# 02_ZYNQ_PS-BANK500-501.net
KiCad netlist of a schematic drawn in Altium Designer
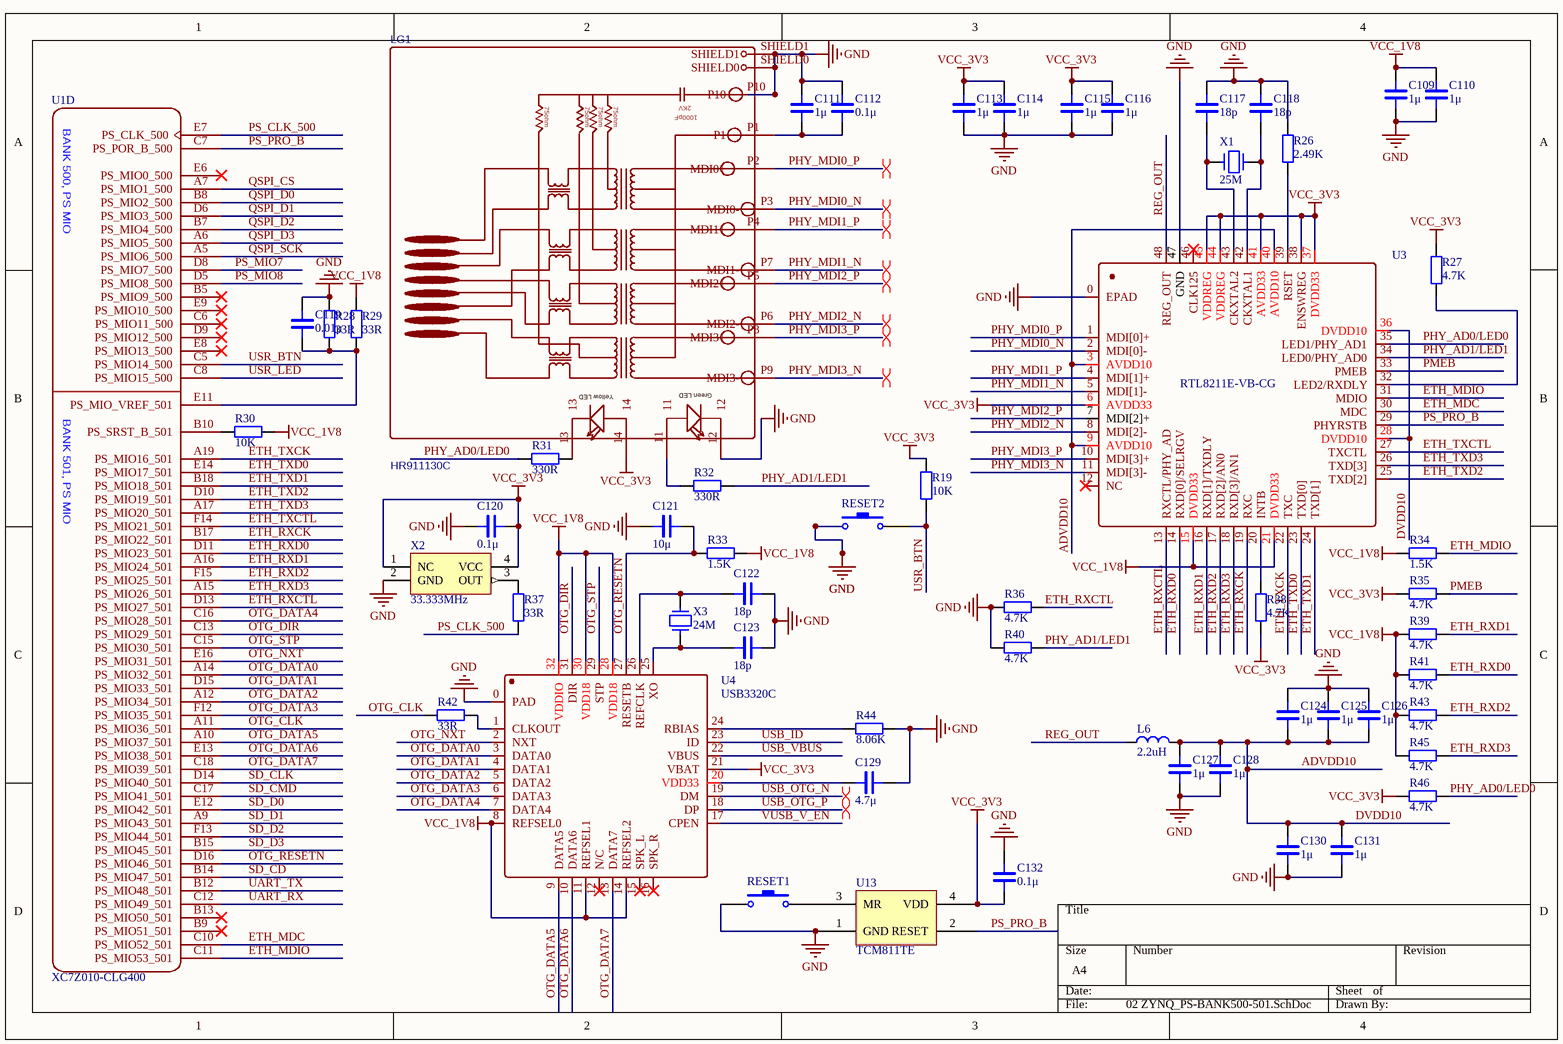
[diagram p0: 02 ZYNQ_PS-BANK500-501.SchDoc]

(export (version "E")
  (design (tool "Eeschema 10.0.6"))
  (components
    (comp (ref "C109")
      (value "1μ")
      (footprint "LC-0402_C")
      (description "Capacitor")
      (libsource (lib "DDR3_xc7z010-clg400") (part "CAP_2"))
    )
    (comp (ref "C110")
      (value "1μ")
      (footprint "LC-0402_C")
      (description "Capacitor")
      (libsource (lib "DDR3_xc7z010-clg400") (part "CAP_2"))
    )
    (comp (ref "C111")
      (value "1μ")
      (footprint "LC-0402_C")
      (description "Capacitor")
      (libsource (lib "DDR3_xc7z010-clg400") (part "CAP_2"))
    )
    (comp (ref "C112")
      (value "0.1μ")
      (footprint "LC-0402_C")
      (description "Capacitor")
      (libsource (lib "DDR3_xc7z010-clg400") (part "CAP_2"))
    )
    (comp (ref "C113")
      (value "1μ")
      (footprint "LC-0402_C")
      (description "Capacitor")
      (libsource (lib "DDR3_xc7z010-clg400") (part "CAP_2"))
    )
    (comp (ref "C114")
      (value "1μ")
      (footprint "LC-0402_C")
      (description "Capacitor")
      (libsource (lib "DDR3_xc7z010-clg400") (part "CAP_2"))
    )
    (comp (ref "C115")
      (value "1μ")
      (footprint "LC-0402_C")
      (description "Capacitor")
      (libsource (lib "DDR3_xc7z010-clg400") (part "CAP_2"))
    )
    (comp (ref "C116")
      (value "1μ")
      (footprint "LC-0402_C")
      (description "Capacitor")
      (libsource (lib "DDR3_xc7z010-clg400") (part "CAP_2"))
    )
    (comp (ref "C117")
      (value "18p")
      (footprint "LC-0402_C")
      (description "Capacitor")
      (libsource (lib "DDR3_xc7z010-clg400") (part "CAP_1"))
    )
    (comp (ref "C118")
      (value "18p")
      (footprint "LC-0402_C")
      (description "Capacitor")
      (libsource (lib "DDR3_xc7z010-clg400") (part "CAP_1"))
    )
    (comp (ref "C119")
      (value "0.01μ")
      (footprint "LC-0402_C")
      (description "Capacitor")
      (libsource (lib "DDR3_xc7z010-clg400") (part "CAP_2"))
    )
    (comp (ref "C120")
      (value "0.1μ")
      (footprint "LC-0402_C")
      (description "Capacitor")
      (libsource (lib "DDR3_xc7z010-clg400") (part "CAP_2"))
    )
    (comp (ref "C121")
      (value "10μ")
      (footprint "LC-0402_C")
      (description "Capacitor")
      (libsource (lib "DDR3_xc7z010-clg400") (part "CAP_2"))
    )
    (comp (ref "C122")
      (value "18p")
      (footprint "LC-0402_C")
      (description "Capacitor")
      (libsource (lib "DDR3_xc7z010-clg400") (part "CAP_1"))
    )
    (comp (ref "C123")
      (value "18p")
      (footprint "LC-0402_C")
      (description "Capacitor")
      (libsource (lib "DDR3_xc7z010-clg400") (part "CAP_1"))
    )
    (comp (ref "C124")
      (value "1μ")
      (footprint "LC-0402_C")
      (description "Capacitor")
      (libsource (lib "DDR3_xc7z010-clg400") (part "CAP_2"))
    )
    (comp (ref "C125")
      (value "1μ")
      (footprint "LC-0402_C")
      (description "Capacitor")
      (libsource (lib "DDR3_xc7z010-clg400") (part "CAP_2"))
    )
    (comp (ref "C126")
      (value "1μ")
      (footprint "LC-0402_C")
      (description "Capacitor")
      (libsource (lib "DDR3_xc7z010-clg400") (part "CAP_2"))
    )
    (comp (ref "C127")
      (value "1μ")
      (footprint "LC-0402_C")
      (description "Capacitor")
      (libsource (lib "DDR3_xc7z010-clg400") (part "CAP_2"))
    )
    (comp (ref "C128")
      (value "1μ")
      (footprint "LC-0402_C")
      (description "Capacitor")
      (libsource (lib "DDR3_xc7z010-clg400") (part "CAP_2"))
    )
    (comp (ref "C129")
      (value "4.7μ")
      (footprint "LC-0402_C")
      (description "Capacitor")
      (libsource (lib "DDR3_xc7z010-clg400") (part "CAP_2"))
    )
    (comp (ref "C130")
      (value "1μ")
      (footprint "LC-0402_C")
      (description "Capacitor")
      (libsource (lib "DDR3_xc7z010-clg400") (part "CAP_2"))
    )
    (comp (ref "C131")
      (value "1μ")
      (footprint "LC-0402_C")
      (description "Capacitor")
      (libsource (lib "DDR3_xc7z010-clg400") (part "CAP_2"))
    )
    (comp (ref "C132")
      (value "0.1μ")
      (footprint "LC-0402_C")
      (description "Capacitor")
      (libsource (lib "DDR3_xc7z010-clg400") (part "CAP_2"))
    )
    (comp (ref "L6")
      (value "2.2uH")
      (footprint "L1008")
      (description "Inductance")
      (libsource (lib "NGFF_M_Key_xc7z010-clg400") (part "INDUCTANCE_1"))
    )
    (comp (ref "LG1")
      (value "HR911130C")
      (footprint "HR911130C")
      (fields (field (name "BOM_SUPPLIER PART") "C50933") (field (name "CONTRIBUTOR") "LCSC"))
      (libsource (lib "AD9363_ZYNQ_V2") (part "HR911130C"))
    )
    (comp (ref "R19")
      (value "10K")
      (footprint "LC-0402_R")
      (description "Resistor")
      (libsource (lib "DDR3_xc7z010-clg400") (part "RES"))
    )
    (comp (ref "R26")
      (value "2.49K")
      (footprint "LC-0402_R")
      (description "Resistor")
      (libsource (lib "") (part "RES_2"))
    )
    (comp (ref "R27")
      (value "4.7K")
      (footprint "LC-0402_R")
      (description "Resistor")
      (libsource (lib "") (part "RES_2"))
    )
    (comp (ref "R28")
      (value "33R")
      (footprint "LC-0402_R")
      (description "Resistor")
      (libsource (lib "") (part "RES_2"))
    )
    (comp (ref "R29")
      (value "33R")
      (footprint "LC-0402_R")
      (description "Resistor")
      (libsource (lib "") (part "RES_2"))
    )
    (comp (ref "R30")
      (value "10K")
      (footprint "LC-0402_R")
      (description "Resistor")
      (libsource (lib "") (part "RES_1"))
    )
    (comp (ref "R31")
      (value "330R")
      (footprint "LC-0402_R")
      (description "Resistor")
      (libsource (lib "") (part "RES_3"))
    )
    (comp (ref "R32")
      (value "330R")
      (footprint "LC-0402_R")
      (description "Resistor")
      (libsource (lib "") (part "RES_1"))
    )
    (comp (ref "R33")
      (value "1.5K")
      (footprint "LC-0402_R")
      (description "Resistor")
      (libsource (lib "") (part "RES_3"))
    )
    (comp (ref "R34")
      (value "1.5K")
      (footprint "LC-0402_R")
      (description "Resistor")
      (libsource (lib "") (part "RES_3"))
    )
    (comp (ref "R35")
      (value "4.7K")
      (footprint "LC-0402_R")
      (description "Resistor")
      (libsource (lib "") (part "RES_3"))
    )
    (comp (ref "R36")
      (value "4.7K")
      (footprint "LC-0402_R")
      (description "Resistor")
      (libsource (lib "") (part "RES_3"))
    )
    (comp (ref "R37")
      (value "33R")
      (footprint "LC-0402_R")
      (description "Resistor")
      (libsource (lib "") (part "RES_2"))
    )
    (comp (ref "R38")
      (value "4.7K")
      (footprint "LC-0402_R")
      (description "Resistor")
      (libsource (lib "") (part "RES_2"))
    )
    (comp (ref "R39")
      (value "4.7K")
      (footprint "LC-0402_R")
      (description "Resistor")
      (libsource (lib "") (part "RES_1"))
    )
    (comp (ref "R40")
      (value "4.7K")
      (footprint "LC-0402_R")
      (description "Resistor")
      (libsource (lib "") (part "RES_3"))
    )
    (comp (ref "R41")
      (value "4.7K")
      (footprint "LC-0402_R")
      (description "Resistor")
      (libsource (lib "") (part "RES_1"))
    )
    (comp (ref "R42")
      (value "33R")
      (footprint "LC-0402_R")
      (description "Resistor")
      (libsource (lib "") (part "RES_3"))
    )
    (comp (ref "R43")
      (value "4.7K")
      (footprint "LC-0402_R")
      (description "Resistor")
      (libsource (lib "") (part "RES_1"))
    )
    (comp (ref "R44")
      (value "8.06K")
      (footprint "LC-0402_R")
      (description "Resistor")
      (libsource (lib "") (part "RES_3"))
    )
    (comp (ref "R45")
      (value "4.7K")
      (footprint "LC-0402_R")
      (description "Resistor")
      (libsource (lib "") (part "RES_1"))
    )
    (comp (ref "R46")
      (value "4.7K")
      (footprint "LC-0402_R")
      (description "Resistor")
      (libsource (lib "") (part "RES_3"))
    )
    (comp (ref "RESET1")
      (value "SW-PB")
      (footprint "开关")
      (description "Switch")
      (fields (field (name "PUBLISHER") "Altium Limited"))
      (libsource (lib "PCB_Project") (part "SW-PB"))
    )
    (comp (ref "RESET2")
      (value "SW-PB")
      (footprint "开关")
      (description "Switch")
      (fields (field (name "PUBLISHER") "Altium Limited"))
      (libsource (lib "M4(3333)") (part "SW-PB"))
    )
    (comp (ref "U1")
      (value "XC7Z010-CLG400")
      (footprint "CLG400-0.8")
      (libsource (lib "DDR3_xc7z010-clg400") (part "XC7Z010-CLG400"))
    )
    (comp (ref "U3")
      (value "RTL8211E-VB-CG")
      (footprint "LC-QFN-48_6x6x04P")
      (libsource (lib "NGFF_M_Key_xc7z010-clg400") (part "RTL8211E-VB-CG"))
    )
    (comp (ref "U4")
      (value "USB3320C")
      (footprint "LC-QFN-32_5x5x05P")
      (libsource (lib "NGFF_M_Key_xc7z010-clg400") (part "USB3320C"))
    )
    (comp (ref "U13")
      (value "TCM811TE")
      (footprint "TCM811TERCTR")
      (libsource (lib "PCB_Project") (part "TCM811TE"))
    )
    (comp (ref "X1")
      (value "25M")
      (footprint "LC-SMD-5032_2P")
      (description "Crystal")
      (libsource (lib "DDR3_xc7z010-clg400") (part "XTAL-2"))
    )
    (comp (ref "X2")
      (value "33.333MHz")
      (footprint "OSC-SMD_4P-L3.2-W2.5-BL")
      (description "Oscillator")
      (libsource (lib "DDR3_xc7z010-clg400") (part "XTAL-4"))
    )
    (comp (ref "X3")
      (value "24M")
      (footprint "LC-SMD-5032_2P")
      (description "Crystal")
      (libsource (lib "DDR3_xc7z010-clg400") (part "XTAL-2"))
    )
  )
  (nets
    (net (code "1") (name "/ADVDD10") (class "Default")
      (node (ref "C124") (pin "1") (pinfunction "1_1") (pintype "passive"))
      (node (ref "C125") (pin "1") (pinfunction "1_1") (pintype "passive"))
      (node (ref "C126") (pin "1") (pinfunction "1_1") (pintype "passive"))
      (node (ref "C127") (pin "2") (pinfunction "2_2") (pintype "passive"))
      (node (ref "C128") (pin "2") (pinfunction "2_2") (pintype "passive"))
      (node (ref "C130") (pin "2") (pinfunction "2_2") (pintype "passive"))
      (node (ref "C131") (pin "2") (pinfunction "2_2") (pintype "passive"))
      (node (ref "L6") (pin "2") (pinfunction "2_2") (pintype "passive"))
      (node (ref "U3") (pin "28") (pinfunction "DVDD10_28") (pintype "passive"))
      (node (ref "U3") (pin "3") (pinfunction "AVDD10_3") (pintype "passive"))
      (node (ref "U3") (pin "36") (pinfunction "DVDD10_36") (pintype "passive"))
      (node (ref "U3") (pin "40") (pinfunction "AVDD10_40") (pintype "passive"))
      (node (ref "U3") (pin "9") (pinfunction "AVDD10_9") (pintype "passive"))
    )
    (net (code "2") (name "/ETH_MDC") (class "Default")
      (node (ref "U1") (pin "C10") (pinfunction "PS_MIO52_501_C10") (pintype "passive"))
      (node (ref "U3") (pin "30") (pinfunction "MDC_30") (pintype "passive"))
    )
    (net (code "3") (name "/ETH_MDIO") (class "Default")
      (node (ref "R34") (pin "2") (pinfunction "2_2") (pintype "passive"))
      (node (ref "U1") (pin "C11") (pinfunction "PS_MIO53_501_C11") (pintype "passive"))
      (node (ref "U3") (pin "31") (pinfunction "MDIO_31") (pintype "passive"))
    )
    (net (code "4") (name "/ETH_RXCK") (class "Default")
      (node (ref "U1") (pin "B17") (pinfunction "PS_MIO22_501_B17") (pintype "passive"))
      (node (ref "U3") (pin "19") (pinfunction "RXC_19") (pintype "passive"))
    )
    (net (code "5") (name "/ETH_RXCTL") (class "Default")
      (node (ref "R36") (pin "2") (pinfunction "2_2") (pintype "passive"))
      (node (ref "U1") (pin "D13") (pinfunction "PS_MIO27_501_D13") (pintype "passive"))
      (node (ref "U3") (pin "13") (pinfunction "RXCTL/PHY_AD_13") (pintype "passive"))
    )
    (net (code "6") (name "/ETH_RXD0") (class "Default")
      (node (ref "R41") (pin "1") (pinfunction "1_1") (pintype "passive"))
      (node (ref "U1") (pin "D11") (pinfunction "PS_MIO23_501_D11") (pintype "passive"))
      (node (ref "U3") (pin "14") (pinfunction "RXD[0]/SELRGV_14") (pintype "passive"))
    )
    (net (code "7") (name "/ETH_RXD1") (class "Default")
      (node (ref "R39") (pin "1") (pinfunction "1_1") (pintype "passive"))
      (node (ref "U1") (pin "A16") (pinfunction "PS_MIO24_501_A16") (pintype "passive"))
      (node (ref "U3") (pin "16") (pinfunction "RXD[1]/TXDLY_16") (pintype "passive"))
    )
    (net (code "8") (name "/ETH_RXD2") (class "Default")
      (node (ref "R43") (pin "1") (pinfunction "1_1") (pintype "passive"))
      (node (ref "U1") (pin "F15") (pinfunction "PS_MIO25_501_F15") (pintype "passive"))
      (node (ref "U3") (pin "17") (pinfunction "RXD[2]/AN0_17") (pintype "passive"))
    )
    (net (code "9") (name "/ETH_RXD3") (class "Default")
      (node (ref "R45") (pin "1") (pinfunction "1_1") (pintype "passive"))
      (node (ref "U1") (pin "A15") (pinfunction "PS_MIO26_501_A15") (pintype "passive"))
      (node (ref "U3") (pin "18") (pinfunction "RXD[3]/AN1_18") (pintype "passive"))
    )
    (net (code "10") (name "/ETH_TXCK") (class "Default")
      (node (ref "U1") (pin "A19") (pinfunction "PS_MIO16_501_A19") (pintype "passive"))
      (node (ref "U3") (pin "22") (pinfunction "TXC_22") (pintype "passive"))
    )
    (net (code "11") (name "/ETH_TXCTL") (class "Default")
      (node (ref "U1") (pin "F14") (pinfunction "PS_MIO21_501_F14") (pintype "passive"))
      (node (ref "U3") (pin "27") (pinfunction "TXCTL_27") (pintype "passive"))
    )
    (net (code "12") (name "/ETH_TXD0") (class "Default")
      (node (ref "U1") (pin "E14") (pinfunction "PS_MIO17_501_E14") (pintype "passive"))
      (node (ref "U3") (pin "23") (pinfunction "TXD[0]_23") (pintype "passive"))
    )
    (net (code "13") (name "/ETH_TXD1") (class "Default")
      (node (ref "U1") (pin "B18") (pinfunction "PS_MIO18_501_B18") (pintype "passive"))
      (node (ref "U3") (pin "24") (pinfunction "TXD[1]_24") (pintype "passive"))
    )
    (net (code "14") (name "/ETH_TXD2") (class "Default")
      (node (ref "U1") (pin "D10") (pinfunction "PS_MIO19_501_D10") (pintype "passive"))
      (node (ref "U3") (pin "25") (pinfunction "TXD[2]_25") (pintype "passive"))
    )
    (net (code "15") (name "/ETH_TXD3") (class "Default")
      (node (ref "U1") (pin "A17") (pinfunction "PS_MIO20_501_A17") (pintype "passive"))
      (node (ref "U3") (pin "26") (pinfunction "TXD[3]_26") (pintype "passive"))
    )
    (net (code "16") (name "/OTG_CLK") (class "Default")
      (node (ref "R42") (pin "1") (pinfunction "1_1") (pintype "passive"))
      (node (ref "U1") (pin "A11") (pinfunction "PS_MIO36_501_A11") (pintype "passive"))
    )
    (net (code "17") (name "/OTG_DATA0") (class "Default")
      (node (ref "U1") (pin "A14") (pinfunction "PS_MIO32_501_A14") (pintype "passive"))
      (node (ref "U4") (pin "3") (pinfunction "DATA0_3") (pintype "passive"))
    )
    (net (code "18") (name "/OTG_DATA1") (class "Default")
      (node (ref "U1") (pin "D15") (pinfunction "PS_MIO33_501_D15") (pintype "passive"))
      (node (ref "U4") (pin "4") (pinfunction "DATA1_4") (pintype "passive"))
    )
    (net (code "19") (name "/OTG_DATA2") (class "Default")
      (node (ref "U1") (pin "A12") (pinfunction "PS_MIO34_501_A12") (pintype "passive"))
      (node (ref "U4") (pin "5") (pinfunction "DATA2_5") (pintype "passive"))
    )
    (net (code "20") (name "/OTG_DATA3") (class "Default")
      (node (ref "U1") (pin "F12") (pinfunction "PS_MIO35_501_F12") (pintype "passive"))
      (node (ref "U4") (pin "6") (pinfunction "DATA3_6") (pintype "passive"))
    )
    (net (code "21") (name "/OTG_DATA4") (class "Default")
      (node (ref "U1") (pin "C16") (pinfunction "PS_MIO28_501_C16") (pintype "passive"))
      (node (ref "U4") (pin "7") (pinfunction "DATA4_7") (pintype "passive"))
    )
    (net (code "22") (name "/OTG_DATA5") (class "Default")
      (node (ref "U1") (pin "A10") (pinfunction "PS_MIO37_501_A10") (pintype "passive"))
      (node (ref "U4") (pin "9") (pinfunction "DATA5_9") (pintype "passive"))
    )
    (net (code "23") (name "/OTG_DATA6") (class "Default")
      (node (ref "U1") (pin "E13") (pinfunction "PS_MIO38_501_E13") (pintype "passive"))
      (node (ref "U4") (pin "10") (pinfunction "DATA6_10") (pintype "passive"))
    )
    (net (code "24") (name "/OTG_DATA7") (class "Default")
      (node (ref "U1") (pin "C18") (pinfunction "PS_MIO39_501_C18") (pintype "passive"))
      (node (ref "U4") (pin "13") (pinfunction "DATA7_13") (pintype "passive"))
    )
    (net (code "25") (name "/OTG_DIR") (class "Default")
      (node (ref "U1") (pin "C13") (pinfunction "PS_MIO29_501_C13") (pintype "passive"))
      (node (ref "U4") (pin "31") (pinfunction "DIR_31") (pintype "passive"))
    )
    (net (code "26") (name "/OTG_NXT") (class "Default")
      (node (ref "U1") (pin "E16") (pinfunction "PS_MIO31_501_E16") (pintype "passive"))
      (node (ref "U4") (pin "2") (pinfunction "NXT_2") (pintype "passive"))
    )
    (net (code "27") (name "/OTG_RESETN") (class "Default")
      (node (ref "C121") (pin "2") (pinfunction "2_2") (pintype "passive"))
      (node (ref "R33") (pin "1") (pinfunction "1_1") (pintype "passive"))
      (node (ref "U1") (pin "D16") (pinfunction "PS_MIO46_501_D16") (pintype "passive"))
      (node (ref "U4") (pin "27") (pinfunction "RESETB_27") (pintype "passive"))
    )
    (net (code "28") (name "/OTG_STP") (class "Default")
      (node (ref "U1") (pin "C15") (pinfunction "PS_MIO30_501_C15") (pintype "passive"))
      (node (ref "U4") (pin "29") (pinfunction "STP_29") (pintype "passive"))
    )
    (net (code "29") (name "/PHY_AD0{slash}LED0") (class "Default")
      (node (ref "R31") (pin "1") (pinfunction "1_1") (pintype "passive"))
      (node (ref "R46") (pin "2") (pinfunction "2_2") (pintype "passive"))
      (node (ref "U3") (pin "35") (pinfunction "LED1/PHY_AD1_35") (pintype "passive"))
    )
    (net (code "30") (name "/PHY_AD1{slash}LED1") (class "Default")
      (node (ref "R32") (pin "1") (pinfunction "1_1") (pintype "passive"))
      (node (ref "R40") (pin "2") (pinfunction "2_2") (pintype "passive"))
      (node (ref "U3") (pin "34") (pinfunction "LED0/PHY_AD0_34") (pintype "passive"))
    )
    (net (code "31") (name "/PHY_MDI0_N") (class "Default")
      (node (ref "LG1") (pin "P3") (pinfunction "MDI0-_P3") (pintype "passive"))
      (node (ref "U3") (pin "2") (pinfunction "MDI[0]-_2") (pintype "passive"))
    )
    (net (code "32") (name "/PHY_MDI0_P") (class "Default")
      (node (ref "LG1") (pin "P2") (pinfunction "MDI0+_P2") (pintype "passive"))
      (node (ref "U3") (pin "1") (pinfunction "MDI[0]+_1") (pintype "passive"))
    )
    (net (code "33") (name "/PHY_MDI1_N") (class "Default")
      (node (ref "LG1") (pin "P7") (pinfunction "MDI1-_P7") (pintype "passive"))
      (node (ref "U3") (pin "5") (pinfunction "MDI[1]-_5") (pintype "passive"))
    )
    (net (code "34") (name "/PHY_MDI1_P") (class "Default")
      (node (ref "LG1") (pin "P4") (pinfunction "MDI1+_P4") (pintype "passive"))
      (node (ref "U3") (pin "4") (pinfunction "MDI[1]+_4") (pintype "passive"))
    )
    (net (code "35") (name "/PHY_MDI2_N") (class "Default")
      (node (ref "LG1") (pin "P6") (pinfunction "MDI2-_P6") (pintype "passive"))
      (node (ref "U3") (pin "8") (pinfunction "MDI[2]-_8") (pintype "passive"))
    )
    (net (code "36") (name "/PHY_MDI2_P") (class "Default")
      (node (ref "LG1") (pin "P5") (pinfunction "MDI2+_P5") (pintype "passive"))
      (node (ref "U3") (pin "7") (pinfunction "MDI[2]+_7") (pintype "passive"))
    )
    (net (code "37") (name "/PHY_MDI3_N") (class "Default")
      (node (ref "LG1") (pin "P9") (pinfunction "MDI3-_P9") (pintype "passive"))
      (node (ref "U3") (pin "11") (pinfunction "MDI[3]-_11") (pintype "passive"))
    )
    (net (code "38") (name "/PHY_MDI3_P") (class "Default")
      (node (ref "LG1") (pin "P8") (pinfunction "MDI3+_P8") (pintype "passive"))
      (node (ref "U3") (pin "10") (pinfunction "MDI[3]+_10") (pintype "passive"))
    )
    (net (code "39") (name "/PMEB") (class "Default")
      (node (ref "R35") (pin "2") (pinfunction "2_2") (pintype "passive"))
      (node (ref "U3") (pin "33") (pinfunction "PMEB_33") (pintype "passive"))
    )
    (net (code "40") (name "/PS_CLK_500") (class "Default")
      (node (ref "R37") (pin "1") (pinfunction "1_1") (pintype "passive"))
      (node (ref "U1") (pin "E7") (pinfunction "PS_CLK_500_E7") (pintype "passive"))
    )
    (net (code "41") (name "/PS_MIO7") (class "Default")
      (node (ref "U1") (pin "D8") (pinfunction "PS_MIO7_500_D8") (pintype "passive"))
    )
    (net (code "42") (name "/PS_MIO8") (class "Default")
      (node (ref "U1") (pin "D5") (pinfunction "PS_MIO8_500_D5") (pintype "passive"))
    )
    (net (code "43") (name "/PS_PRO_B") (class "Default")
      (node (ref "U1") (pin "C7") (pinfunction "PS_POR_B_500_C7") (pintype "passive"))
      (node (ref "U13") (pin "2") (pinfunction "RESET_2") (pintype "passive"))
      (node (ref "U3") (pin "29") (pinfunction "PHYRSTB_29") (pintype "passive"))
    )
    (net (code "44") (name "/QSPI_CS") (class "Default")
      (node (ref "U1") (pin "A7") (pinfunction "PS_MIO1_500_A7") (pintype "passive"))
    )
    (net (code "45") (name "/QSPI_D0") (class "Default")
      (node (ref "U1") (pin "B8") (pinfunction "PS_MIO2_500_B8") (pintype "passive"))
    )
    (net (code "46") (name "/QSPI_D1") (class "Default")
      (node (ref "U1") (pin "D6") (pinfunction "PS_MIO3_500_D6") (pintype "passive"))
    )
    (net (code "47") (name "/QSPI_D2") (class "Default")
      (node (ref "U1") (pin "B7") (pinfunction "PS_MIO4_500_B7") (pintype "passive"))
    )
    (net (code "48") (name "/QSPI_D3") (class "Default")
      (node (ref "U1") (pin "A6") (pinfunction "PS_MIO5_500_A6") (pintype "passive"))
    )
    (net (code "49") (name "/QSPI_SCK") (class "Default")
      (node (ref "U1") (pin "A5") (pinfunction "PS_MIO6_500_A5") (pintype "passive"))
    )
    (net (code "50") (name "/REG_OUT") (class "Default")
      (node (ref "L6") (pin "1") (pinfunction "1_1") (pintype "passive"))
      (node (ref "U3") (pin "48") (pinfunction "REG_OUT_48") (pintype "passive"))
    )
    (net (code "51") (name "/SD_CD") (class "Default")
      (node (ref "U1") (pin "B14") (pinfunction "PS_MIO47_501_B14") (pintype "passive"))
    )
    (net (code "52") (name "/SD_CLK") (class "Default")
      (node (ref "U1") (pin "D14") (pinfunction "PS_MIO40_501_D14") (pintype "passive"))
    )
    (net (code "53") (name "/SD_CMD") (class "Default")
      (node (ref "U1") (pin "C17") (pinfunction "PS_MIO41_501_C17") (pintype "passive"))
    )
    (net (code "54") (name "/SD_D0") (class "Default")
      (node (ref "U1") (pin "E12") (pinfunction "PS_MIO42_501_E12") (pintype "passive"))
    )
    (net (code "55") (name "/SD_D1") (class "Default")
      (node (ref "U1") (pin "A9") (pinfunction "PS_MIO43_501_A9") (pintype "passive"))
    )
    (net (code "56") (name "/SD_D2") (class "Default")
      (node (ref "U1") (pin "F13") (pinfunction "PS_MIO44_501_F13") (pintype "passive"))
    )
    (net (code "57") (name "/SD_D3") (class "Default")
      (node (ref "U1") (pin "B15") (pinfunction "PS_MIO45_501_B15") (pintype "passive"))
    )
    (net (code "58") (name "/UART_RX") (class "Default")
      (node (ref "U1") (pin "C12") (pinfunction "PS_MIO49_501_C12") (pintype "passive"))
    )
    (net (code "59") (name "/UART_TX") (class "Default")
      (node (ref "U1") (pin "B12") (pinfunction "PS_MIO48_501_B12") (pintype "passive"))
    )
    (net (code "60") (name "/USB_ID") (class "Default")
      (node (ref "U4") (pin "23") (pinfunction "ID_23") (pintype "passive"))
    )
    (net (code "61") (name "/USB_OTG_N") (class "Default")
      (node (ref "U4") (pin "19") (pinfunction "DM_19") (pintype "passive"))
    )
    (net (code "62") (name "/USB_OTG_P") (class "Default")
      (node (ref "U4") (pin "18") (pinfunction "DP_18") (pintype "passive"))
    )
    (net (code "63") (name "/USB_VBUS") (class "Default")
      (node (ref "U4") (pin "22") (pinfunction "VBUS_22") (pintype "passive"))
    )
    (net (code "64") (name "/USR_BTN") (class "Default")
      (node (ref "R19") (pin "2") (pinfunction "2_2") (pintype "passive"))
      (node (ref "RESET2") (pin "2") (pinfunction "2_2") (pintype "passive"))
      (node (ref "U1") (pin "C5") (pinfunction "PS_MIO14_500_C5") (pintype "passive"))
    )
    (net (code "65") (name "/USR_LED") (class "Default")
      (node (ref "U1") (pin "C8") (pinfunction "PS_MIO15_500_C8") (pintype "passive"))
    )
    (net (code "66") (name "/VUSB_V_EN") (class "Default")
      (node (ref "U4") (pin "17") (pinfunction "CPEN_17") (pintype "passive"))
    )
    (net (code "67") (name "GND") (class "Default")
      (node (ref "C109") (pin "1") (pinfunction "1_1") (pintype "passive"))
      (node (ref "C110") (pin "1") (pinfunction "1_1") (pintype "passive"))
      (node (ref "C111") (pin "2") (pinfunction "2_2") (pintype "passive"))
      (node (ref "C112") (pin "2") (pinfunction "2_2") (pintype "passive"))
      (node (ref "C113") (pin "1") (pinfunction "1_1") (pintype "passive"))
      (node (ref "C114") (pin "1") (pinfunction "1_1") (pintype "passive"))
      (node (ref "C115") (pin "1") (pinfunction "1_1") (pintype "passive"))
      (node (ref "C116") (pin "1") (pinfunction "1_1") (pintype "passive"))
      (node (ref "C117") (pin "2") (pinfunction "2_2") (pintype "passive"))
      (node (ref "C118") (pin "2") (pinfunction "2_2") (pintype "passive"))
      (node (ref "C119") (pin "1") (pinfunction "1_1") (pintype "passive"))
      (node (ref "C120") (pin "2") (pinfunction "2_2") (pintype "passive"))
      (node (ref "C121") (pin "1") (pinfunction "1_1") (pintype "passive"))
      (node (ref "C122") (pin "2") (pinfunction "2_2") (pintype "passive"))
      (node (ref "C123") (pin "2") (pinfunction "2_2") (pintype "passive"))
      (node (ref "C124") (pin "2") (pinfunction "2_2") (pintype "passive"))
      (node (ref "C125") (pin "2") (pinfunction "2_2") (pintype "passive"))
      (node (ref "C126") (pin "2") (pinfunction "2_2") (pintype "passive"))
      (node (ref "C127") (pin "1") (pinfunction "1_1") (pintype "passive"))
      (node (ref "C128") (pin "1") (pinfunction "1_1") (pintype "passive"))
      (node (ref "C129") (pin "2") (pinfunction "2_2") (pintype "passive"))
      (node (ref "C130") (pin "1") (pinfunction "1_1") (pintype "passive"))
      (node (ref "C131") (pin "1") (pinfunction "1_1") (pintype "passive"))
      (node (ref "C132") (pin "2") (pinfunction "2_2") (pintype "passive"))
      (node (ref "LG1") (pin "12") (pinfunction "12_12") (pintype "passive"))
      (node (ref "LG1") (pin "P10") (pinfunction "P10_P10") (pintype "passive"))
      (node (ref "LG1") (pin "SHIELD0") (pinfunction "SHIELD0_SHIELD0") (pintype "passive"))
      (node (ref "LG1") (pin "SHIELD1") (pinfunction "SHIELD1_SHIELD1") (pintype "passive"))
      (node (ref "R26") (pin "2") (pinfunction "2_2") (pintype "passive"))
      (node (ref "R28") (pin "2") (pinfunction "2_2") (pintype "passive"))
      (node (ref "R36") (pin "1") (pinfunction "1_1") (pintype "passive"))
      (node (ref "R40") (pin "1") (pinfunction "1_1") (pintype "passive"))
      (node (ref "R44") (pin "2") (pinfunction "2_2") (pintype "passive"))
      (node (ref "RESET1") (pin "1") (pinfunction "1_1") (pintype "passive"))
      (node (ref "RESET2") (pin "1") (pinfunction "1_1") (pintype "passive"))
      (node (ref "U13") (pin "1") (pinfunction "GND_1") (pintype "passive"))
      (node (ref "U3") (pin "0") (pinfunction "EPAD_0") (pintype "passive"))
      (node (ref "U3") (pin "47") (pinfunction "GND_47") (pintype "passive"))
      (node (ref "U4") (pin "0") (pinfunction "PAD_0") (pintype "passive"))
      (node (ref "X2") (pin "2") (pinfunction "GND_2") (pintype "power_in"))
    )
    (net (code "68") (name "Net-(C111-Pad1)") (class "Default")
      (node (ref "C111") (pin "1") (pinfunction "1_1") (pintype "passive"))
      (node (ref "C112") (pin "1") (pinfunction "1_1") (pintype "passive"))
      (node (ref "LG1") (pin "P1") (pinfunction "P1_P1") (pintype "passive"))
    )
    (net (code "69") (name "Net-(LG1-Pad11)") (class "Default")
      (node (ref "LG1") (pin "11") (pinfunction "11_11") (pintype "passive"))
      (node (ref "R32") (pin "2") (pinfunction "2_2") (pintype "passive"))
    )
    (net (code "70") (name "Net-(LG1-Pad13)") (class "Default")
      (node (ref "LG1") (pin "13") (pinfunction "13_13") (pintype "passive"))
      (node (ref "R31") (pin "2") (pinfunction "2_2") (pintype "passive"))
    )
    (net (code "71") (name "Net-(U1D-PS_MIO_VREF_501)") (class "Default")
      (node (ref "C119") (pin "2") (pinfunction "2_2") (pintype "passive"))
      (node (ref "R28") (pin "1") (pinfunction "1_1") (pintype "passive"))
      (node (ref "R29") (pin "1") (pinfunction "1_1") (pintype "passive"))
      (node (ref "U1") (pin "E11") (pinfunction "PS_MIO_VREF_501_E11") (pintype "passive"))
    )
    (net (code "72") (name "Net-(U1D-PS_SRST_B_501)") (class "Default")
      (node (ref "R30") (pin "2") (pinfunction "2_2") (pintype "passive"))
      (node (ref "U1") (pin "B10") (pinfunction "PS_SRST_B_501_B10") (pintype "passive"))
    )
    (net (code "73") (name "Net-(U3-CKXTAL1)") (class "Default")
      (node (ref "C118") (pin "1") (pinfunction "1_1") (pintype "passive"))
      (node (ref "U3") (pin "42") (pinfunction "CKXTAL1_42") (pintype "passive"))
      (node (ref "X1") (pin "2") (pinfunction "2_2") (pintype "passive"))
    )
    (net (code "74") (name "Net-(U3-CKXTAL2)") (class "Default")
      (node (ref "C117") (pin "1") (pinfunction "1_1") (pintype "passive"))
      (node (ref "U3") (pin "43") (pinfunction "CKXTAL2_43") (pintype "passive"))
      (node (ref "X1") (pin "1") (pinfunction "1_1") (pintype "passive"))
    )
    (net (code "75") (name "Net-(U3-INTB)") (class "Default")
      (node (ref "R38") (pin "2") (pinfunction "2_2") (pintype "passive"))
      (node (ref "U3") (pin "20") (pinfunction "INTB_20") (pintype "passive"))
    )
    (net (code "76") (name "Net-(U3-LED2{slash}RXDLY)") (class "Default")
      (node (ref "R27") (pin "1") (pinfunction "1_1") (pintype "passive"))
      (node (ref "U3") (pin "32") (pinfunction "LED2/RXDLY_32") (pintype "passive"))
    )
    (net (code "77") (name "Net-(U3-RSET)") (class "Default")
      (node (ref "R26") (pin "1") (pinfunction "1_1") (pintype "passive"))
      (node (ref "U3") (pin "39") (pinfunction "RSET_39") (pintype "passive"))
    )
    (net (code "78") (name "Net-(U4-CLKOUT)") (class "Default")
      (node (ref "R42") (pin "2") (pinfunction "2_2") (pintype "passive"))
      (node (ref "U4") (pin "1") (pinfunction "CLKOUT_1") (pintype "passive"))
    )
    (net (code "79") (name "Net-(U4-RBIAS)") (class "Default")
      (node (ref "R44") (pin "1") (pinfunction "1_1") (pintype "passive"))
      (node (ref "U4") (pin "24") (pinfunction "RBIAS_24") (pintype "passive"))
    )
    (net (code "80") (name "Net-(U4-REFCLK)") (class "Default")
      (node (ref "C122") (pin "1") (pinfunction "1_1") (pintype "passive"))
      (node (ref "U4") (pin "26") (pinfunction "REFCLK_26") (pintype "passive"))
      (node (ref "X3") (pin "1") (pinfunction "1_1") (pintype "passive"))
    )
    (net (code "81") (name "Net-(U4-VDD33)") (class "Default")
      (node (ref "C129") (pin "1") (pinfunction "1_1") (pintype "passive"))
      (node (ref "U4") (pin "20") (pinfunction "VDD33_20") (pintype "passive"))
    )
    (net (code "82") (name "Net-(U4-XO)") (class "Default")
      (node (ref "C123") (pin "1") (pinfunction "1_1") (pintype "passive"))
      (node (ref "U4") (pin "25") (pinfunction "XO_25") (pintype "passive"))
      (node (ref "X3") (pin "2") (pinfunction "2_2") (pintype "passive"))
    )
    (net (code "83") (name "Net-(U13-MR)") (class "Default")
      (node (ref "RESET1") (pin "2") (pinfunction "2_2") (pintype "passive"))
      (node (ref "U13") (pin "3") (pinfunction "MR_3") (pintype "passive"))
    )
    (net (code "84") (name "Net-(X2-OUT)") (class "Default")
      (node (ref "R37") (pin "2") (pinfunction "2_2") (pintype "passive"))
      (node (ref "X2") (pin "3") (pinfunction "OUT_3") (pintype "output"))
    )
    (net (code "85") (name "VCC_1V8") (class "Default")
      (node (ref "C109") (pin "2") (pinfunction "2_2") (pintype "passive"))
      (node (ref "C110") (pin "2") (pinfunction "2_2") (pintype "passive"))
      (node (ref "R29") (pin "2") (pinfunction "2_2") (pintype "passive"))
      (node (ref "R30") (pin "1") (pinfunction "1_1") (pintype "passive"))
      (node (ref "R33") (pin "2") (pinfunction "2_2") (pintype "passive"))
      (node (ref "R34") (pin "1") (pinfunction "1_1") (pintype "passive"))
      (node (ref "R39") (pin "2") (pinfunction "2_2") (pintype "passive"))
      (node (ref "R41") (pin "2") (pinfunction "2_2") (pintype "passive"))
      (node (ref "R43") (pin "2") (pinfunction "2_2") (pintype "passive"))
      (node (ref "R45") (pin "2") (pinfunction "2_2") (pintype "passive"))
      (node (ref "U3") (pin "15") (pinfunction "DVDD33_15") (pintype "passive"))
      (node (ref "U3") (pin "21") (pinfunction "DVDD33_21") (pintype "passive"))
      (node (ref "U4") (pin "11") (pinfunction "REFSEL1_11") (pintype "passive"))
      (node (ref "U4") (pin "14") (pinfunction "REFSEL2_14") (pintype "passive"))
      (node (ref "U4") (pin "28") (pinfunction "VDD18_28") (pintype "passive"))
      (node (ref "U4") (pin "30") (pinfunction "VDD18_30") (pintype "passive"))
      (node (ref "U4") (pin "32") (pinfunction "VDDIO_32") (pintype "passive"))
      (node (ref "U4") (pin "8") (pinfunction "REFSEL0_8") (pintype "passive"))
    )
    (net (code "86") (name "VCC_3V3") (class "Default")
      (node (ref "C113") (pin "2") (pinfunction "2_2") (pintype "passive"))
      (node (ref "C114") (pin "2") (pinfunction "2_2") (pintype "passive"))
      (node (ref "C115") (pin "2") (pinfunction "2_2") (pintype "passive"))
      (node (ref "C116") (pin "2") (pinfunction "2_2") (pintype "passive"))
      (node (ref "C120") (pin "1") (pinfunction "1_1") (pintype "passive"))
      (node (ref "C132") (pin "1") (pinfunction "1_1") (pintype "passive"))
      (node (ref "LG1") (pin "14") (pinfunction "14_14") (pintype "passive"))
      (node (ref "R19") (pin "1") (pinfunction "1_1") (pintype "passive"))
      (node (ref "R27") (pin "2") (pinfunction "2_2") (pintype "passive"))
      (node (ref "R35") (pin "1") (pinfunction "1_1") (pintype "passive"))
      (node (ref "R38") (pin "1") (pinfunction "1_1") (pintype "passive"))
      (node (ref "R46") (pin "1") (pinfunction "1_1") (pintype "passive"))
      (node (ref "U13") (pin "4") (pinfunction "VDD_4") (pintype "passive"))
      (node (ref "U3") (pin "37") (pinfunction "DVDD33_37") (pintype "passive"))
      (node (ref "U3") (pin "38") (pinfunction "ENSWREG_38") (pintype "passive"))
      (node (ref "U3") (pin "41") (pinfunction "AVDD33_41") (pintype "passive"))
      (node (ref "U3") (pin "44") (pinfunction "VDDREG_44") (pintype "passive"))
      (node (ref "U3") (pin "45") (pinfunction "VDDREG_45") (pintype "passive"))
      (node (ref "U3") (pin "6") (pinfunction "AVDD33_6") (pintype "passive"))
      (node (ref "U4") (pin "21") (pinfunction "VBAT_21") (pintype "passive"))
      (node (ref "X2") (pin "1") (pinfunction "NC_1") (pintype "passive"))
      (node (ref "X2") (pin "4") (pinfunction "VCC_4") (pintype "power_in"))
    )
    (net (code "87") (name "unconnected-(U1D-PS_MIO0_500-PadE6)") (class "Default")
      (node (ref "U1") (pin "E6") (pinfunction "PS_MIO0_500_E6") (pintype "passive+no_connect"))
    )
    (net (code "88") (name "unconnected-(U1D-PS_MIO9_500-PadB5)") (class "Default")
      (node (ref "U1") (pin "B5") (pinfunction "PS_MIO9_500_B5") (pintype "passive+no_connect"))
    )
    (net (code "89") (name "unconnected-(U1D-PS_MIO10_500-PadE9)") (class "Default")
      (node (ref "U1") (pin "E9") (pinfunction "PS_MIO10_500_E9") (pintype "passive+no_connect"))
    )
    (net (code "90") (name "unconnected-(U1D-PS_MIO11_500-PadC6)") (class "Default")
      (node (ref "U1") (pin "C6") (pinfunction "PS_MIO11_500_C6") (pintype "passive+no_connect"))
    )
    (net (code "91") (name "unconnected-(U1D-PS_MIO12_500-PadD9)") (class "Default")
      (node (ref "U1") (pin "D9") (pinfunction "PS_MIO12_500_D9") (pintype "passive+no_connect"))
    )
    (net (code "92") (name "unconnected-(U1D-PS_MIO13_500-PadE8)") (class "Default")
      (node (ref "U1") (pin "E8") (pinfunction "PS_MIO13_500_E8") (pintype "passive+no_connect"))
    )
    (net (code "93") (name "unconnected-(U1D-PS_MIO50_501-PadB13)") (class "Default")
      (node (ref "U1") (pin "B13") (pinfunction "PS_MIO50_501_B13") (pintype "passive+no_connect"))
    )
    (net (code "94") (name "unconnected-(U1D-PS_MIO51_501-PadB9)") (class "Default")
      (node (ref "U1") (pin "B9") (pinfunction "PS_MIO51_501_B9") (pintype "passive+no_connect"))
    )
    (net (code "95") (name "unconnected-(U3-CLK125-Pad46)") (class "Default")
      (node (ref "U3") (pin "46") (pinfunction "CLK125_46") (pintype "passive+no_connect"))
    )
    (net (code "96") (name "unconnected-(U3-NC-Pad12)") (class "Default")
      (node (ref "U3") (pin "12") (pinfunction "NC_12") (pintype "passive+no_connect"))
    )
    (net (code "97") (name "unconnected-(U4-N{slash}C-Pad12)") (class "Default")
      (node (ref "U4") (pin "12") (pinfunction "N/C_12") (pintype "passive+no_connect"))
    )
    (net (code "98") (name "unconnected-(U4-SPK_L-Pad15)") (class "Default")
      (node (ref "U4") (pin "15") (pinfunction "SPK_L_15") (pintype "passive+no_connect"))
    )
    (net (code "99") (name "unconnected-(U4-SPK_R-Pad16)") (class "Default")
      (node (ref "U4") (pin "16") (pinfunction "SPK_R_16") (pintype "passive+no_connect"))
    )
  )
)
